# RFUSBtoDB15Adapter.net
KiCad netlist of a schematic drawn in EAGLE
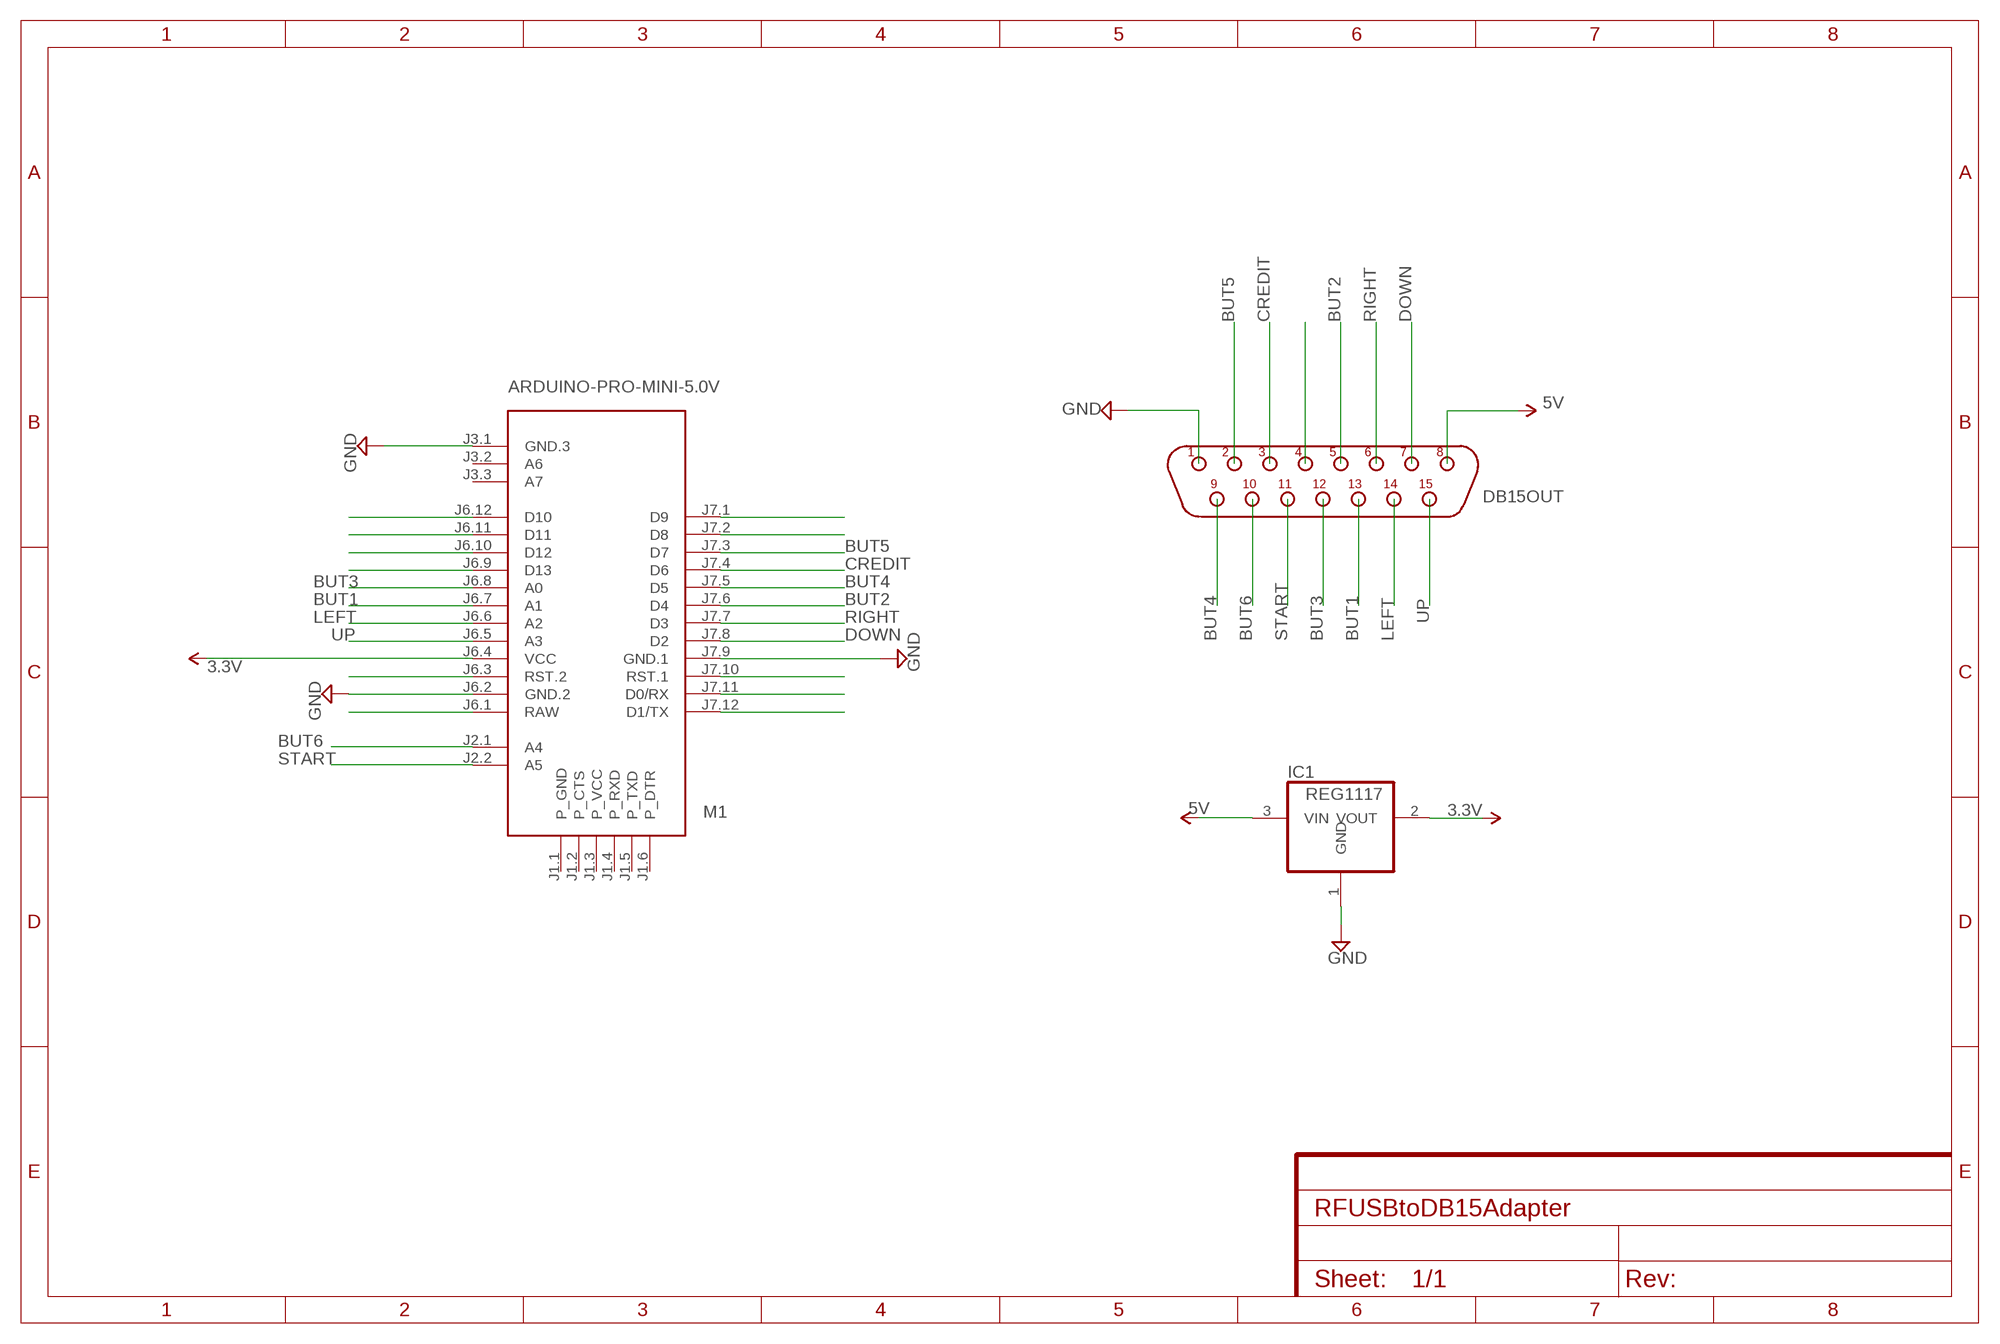
[diagram p0: schematic, sheet 1]

(export (version "E")
  (design (tool "Eeschema 10.0.6"))
  (components
    (comp (ref "DB15OUT")
      (value "DB15M/90")
      (footprint "eagle-import:D-15M_90")
      (libsource (lib "eagle-import") (part "DB15M/90"))
    )
    (comp (ref "IC1")
      (value "REG1117")
      (footprint "eagle-import:SOT223")
      (libsource (lib "eagle-import") (part "REG1117"))
    )
    (comp (ref "M1")
      (value "ARDUINO-PRO-MINI-5.0V")
      (footprint "eagle-import:ARDUINO-PRO-MINI")
      (libsource (lib "eagle-import") (part "ARDUINO-PRO-MINI-5.0V"))
    )
  )
  (nets
    (net (code "1") (name "/BUT1") (class "Default")
      (node (ref "DB15OUT") (pin "13") (pinfunction "13_13") (pintype "passive"))
      (node (ref "M1") (pin "J6.7") (pinfunction "A1_J6.7") (pintype "bidirectional"))
    )
    (net (code "2") (name "/BUT2") (class "Default")
      (node (ref "DB15OUT") (pin "5") (pinfunction "5_5") (pintype "passive"))
      (node (ref "M1") (pin "J7.6") (pinfunction "D4_J7.6") (pintype "bidirectional"))
    )
    (net (code "3") (name "/BUT3") (class "Default")
      (node (ref "DB15OUT") (pin "12") (pinfunction "12_12") (pintype "passive"))
      (node (ref "M1") (pin "J6.8") (pinfunction "A0_J6.8") (pintype "bidirectional"))
    )
    (net (code "4") (name "/BUT4") (class "Default")
      (node (ref "DB15OUT") (pin "9") (pinfunction "9_9") (pintype "passive"))
      (node (ref "M1") (pin "J7.5") (pinfunction "D5_J7.5") (pintype "bidirectional"))
    )
    (net (code "5") (name "/BUT5") (class "Default")
      (node (ref "DB15OUT") (pin "2") (pinfunction "2_2") (pintype "passive"))
      (node (ref "M1") (pin "J7.3") (pinfunction "D7_J7.3") (pintype "bidirectional"))
    )
    (net (code "6") (name "/BUT6") (class "Default")
      (node (ref "DB15OUT") (pin "10") (pinfunction "10_10") (pintype "passive"))
      (node (ref "M1") (pin "J2.1") (pinfunction "A4_J2.1") (pintype "bidirectional"))
    )
    (net (code "7") (name "/CREDIT") (class "Default")
      (node (ref "DB15OUT") (pin "3") (pinfunction "3_3") (pintype "passive"))
      (node (ref "M1") (pin "J7.4") (pinfunction "D6_J7.4") (pintype "bidirectional"))
    )
    (net (code "8") (name "/DOWN") (class "Default")
      (node (ref "DB15OUT") (pin "7") (pinfunction "7_7") (pintype "passive"))
      (node (ref "M1") (pin "J7.8") (pinfunction "D2_J7.8") (pintype "bidirectional"))
    )
    (net (code "9") (name "/LEFT") (class "Default")
      (node (ref "DB15OUT") (pin "14") (pinfunction "14_14") (pintype "passive"))
      (node (ref "M1") (pin "J6.6") (pinfunction "A2_J6.6") (pintype "bidirectional"))
    )
    (net (code "10") (name "/RIGHT") (class "Default")
      (node (ref "DB15OUT") (pin "6") (pinfunction "6_6") (pintype "passive"))
      (node (ref "M1") (pin "J7.7") (pinfunction "D3_J7.7") (pintype "bidirectional"))
    )
    (net (code "11") (name "/START") (class "Default")
      (node (ref "DB15OUT") (pin "11") (pinfunction "11_11") (pintype "passive"))
      (node (ref "M1") (pin "J2.2") (pinfunction "A5_J2.2") (pintype "bidirectional"))
    )
    (net (code "12") (name "/UP") (class "Default")
      (node (ref "DB15OUT") (pin "15") (pinfunction "15_15") (pintype "passive"))
      (node (ref "M1") (pin "J6.5") (pinfunction "A3_J6.5") (pintype "bidirectional"))
    )
    (net (code "13") (name "3.3V") (class "Default")
      (node (ref "IC1") (pin "2") (pinfunction "VOUT_2") (pintype "output"))
      (node (ref "M1") (pin "J6.4") (pinfunction "VCC_J6.4") (pintype "power_in"))
    )
    (net (code "14") (name "5V") (class "Default")
      (node (ref "DB15OUT") (pin "8") (pinfunction "8_8") (pintype "passive"))
      (node (ref "IC1") (pin "3") (pinfunction "VIN_3") (pintype "input"))
    )
    (net (code "15") (name "GND") (class "Default")
      (node (ref "DB15OUT") (pin "1") (pinfunction "1_1") (pintype "passive"))
      (node (ref "IC1") (pin "1") (pinfunction "GND_1") (pintype "power_in"))
      (node (ref "M1") (pin "J3.1") (pinfunction "GND.3_J3.1") (pintype "bidirectional"))
      (node (ref "M1") (pin "J6.2") (pinfunction "GND.2_J6.2") (pintype "power_in"))
      (node (ref "M1") (pin "J7.9") (pinfunction "GND.1_J7.9") (pintype "power_in"))
    )
    (net (code "16") (name "unconnected-(DB15OUT-Pad4)") (class "Default")
      (node (ref "DB15OUT") (pin "4") (pinfunction "4_4") (pintype "passive"))
    )
    (net (code "17") (name "unconnected-(M1-A6-PadJ3.2)") (class "Default")
      (node (ref "M1") (pin "J3.2") (pinfunction "A6_J3.2") (pintype "bidirectional"))
    )
    (net (code "18") (name "unconnected-(M1-A7-PadJ3.3)") (class "Default")
      (node (ref "M1") (pin "J3.3") (pinfunction "A7_J3.3") (pintype "bidirectional"))
    )
    (net (code "19") (name "unconnected-(M1-D0{slash}RX-PadJ7.11)") (class "Default")
      (node (ref "M1") (pin "J7.11") (pinfunction "D0/RX_J7.11") (pintype "bidirectional"))
    )
    (net (code "20") (name "unconnected-(M1-D1{slash}TX-PadJ7.12)") (class "Default")
      (node (ref "M1") (pin "J7.12") (pinfunction "D1/TX_J7.12") (pintype "bidirectional"))
    )
    (net (code "21") (name "unconnected-(M1-D8-PadJ7.2)") (class "Default")
      (node (ref "M1") (pin "J7.2") (pinfunction "D8_J7.2") (pintype "bidirectional"))
    )
    (net (code "22") (name "unconnected-(M1-D9-PadJ7.1)") (class "Default")
      (node (ref "M1") (pin "J7.1") (pinfunction "D9_J7.1") (pintype "bidirectional"))
    )
    (net (code "23") (name "unconnected-(M1-D10-PadJ6.12)") (class "Default")
      (node (ref "M1") (pin "J6.12") (pinfunction "D10_J6.12") (pintype "bidirectional"))
    )
    (net (code "24") (name "unconnected-(M1-D11-PadJ6.11)") (class "Default")
      (node (ref "M1") (pin "J6.11") (pinfunction "D11_J6.11") (pintype "bidirectional"))
    )
    (net (code "25") (name "unconnected-(M1-D12-PadJ6.10)") (class "Default")
      (node (ref "M1") (pin "J6.10") (pinfunction "D12_J6.10") (pintype "bidirectional"))
    )
    (net (code "26") (name "unconnected-(M1-D13-PadJ6.9)") (class "Default")
      (node (ref "M1") (pin "J6.9") (pinfunction "D13_J6.9") (pintype "bidirectional"))
    )
    (net (code "27") (name "unconnected-(M1-P_CTS-PadJ1.2)") (class "Default")
      (node (ref "M1") (pin "J1.2") (pinfunction "P_CTS_J1.2") (pintype "bidirectional"))
    )
    (net (code "28") (name "unconnected-(M1-P_DTR-PadJ1.6)") (class "Default")
      (node (ref "M1") (pin "J1.6") (pinfunction "P_DTR_J1.6") (pintype "bidirectional"))
    )
    (net (code "29") (name "unconnected-(M1-P_GND-PadJ1.1)") (class "Default")
      (node (ref "M1") (pin "J1.1") (pinfunction "P_GND_J1.1") (pintype "bidirectional"))
    )
    (net (code "30") (name "unconnected-(M1-P_RXD-PadJ1.4)") (class "Default")
      (node (ref "M1") (pin "J1.4") (pinfunction "P_RXD_J1.4") (pintype "bidirectional"))
    )
    (net (code "31") (name "unconnected-(M1-P_TXD-PadJ1.5)") (class "Default")
      (node (ref "M1") (pin "J1.5") (pinfunction "P_TXD_J1.5") (pintype "bidirectional"))
    )
    (net (code "32") (name "unconnected-(M1-P_VCC-PadJ1.3)") (class "Default")
      (node (ref "M1") (pin "J1.3") (pinfunction "P_VCC_J1.3") (pintype "bidirectional"))
    )
    (net (code "33") (name "unconnected-(M1-RAW-PadJ6.1)") (class "Default")
      (node (ref "M1") (pin "J6.1") (pinfunction "RAW_J6.1") (pintype "power_in"))
    )
    (net (code "34") (name "unconnected-(M1-RST.1-PadJ7.10)") (class "Default")
      (node (ref "M1") (pin "J7.10") (pinfunction "RST.1_J7.10") (pintype "bidirectional"))
    )
    (net (code "35") (name "unconnected-(M1-RST.2-PadJ6.3)") (class "Default")
      (node (ref "M1") (pin "J6.3") (pinfunction "RST.2_J6.3") (pintype "bidirectional"))
    )
  )
)
